# trigger_interface.net
KiCad netlist of a schematic drawn in Altium Designer
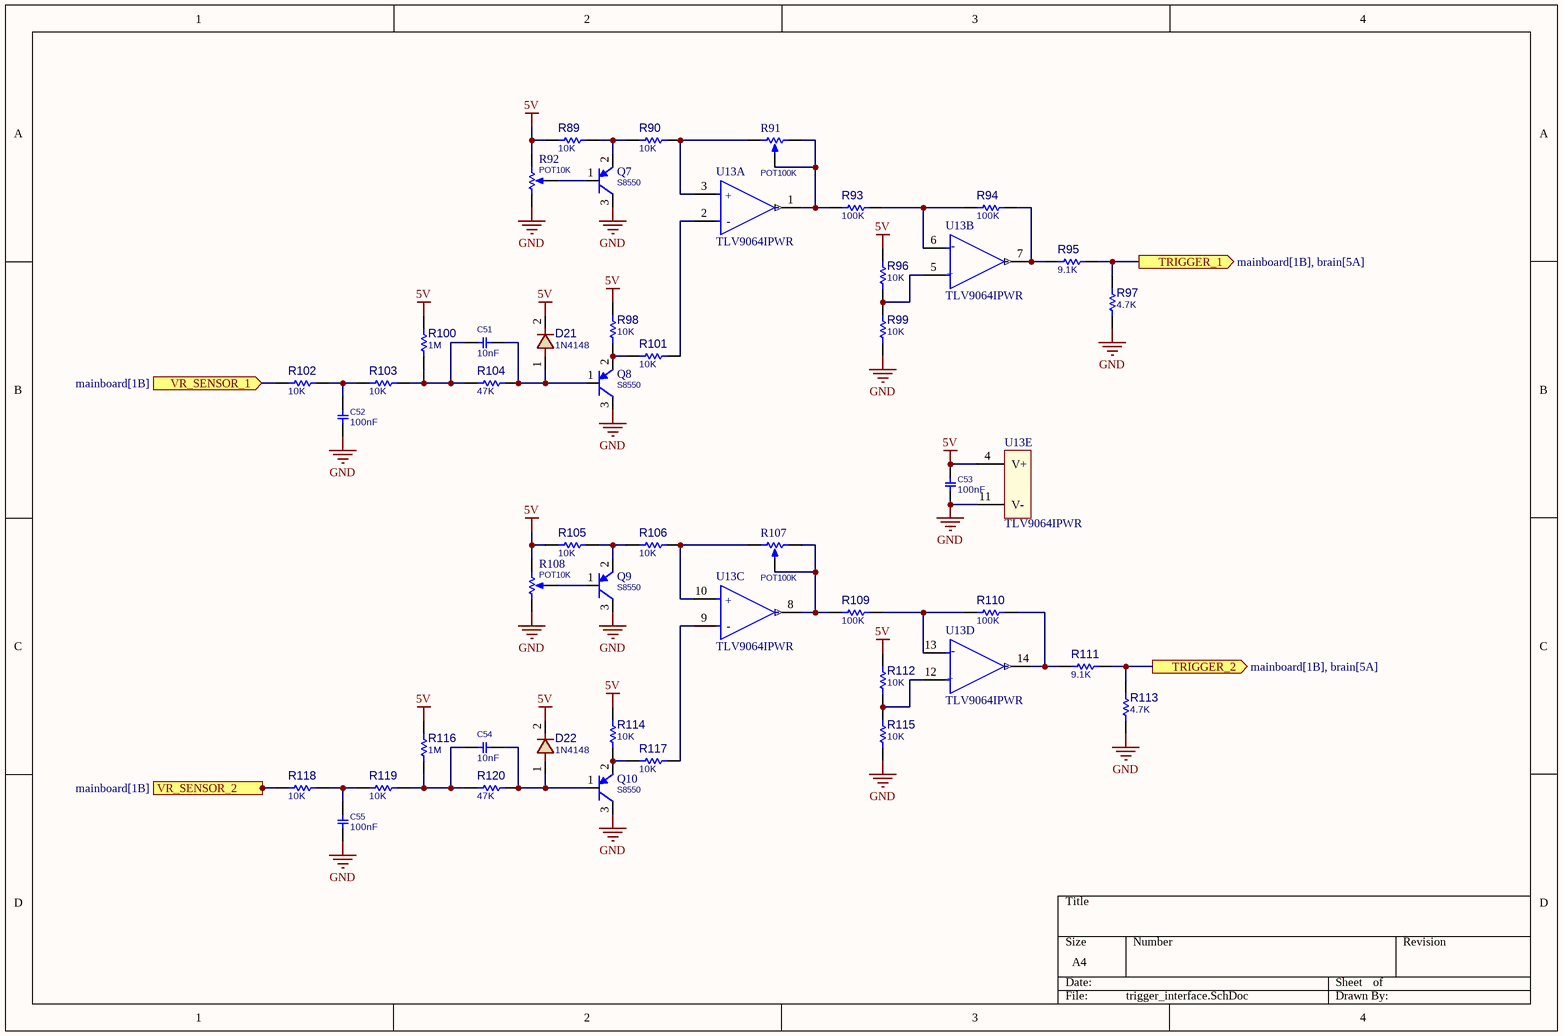
[diagram p0: trigger_interface.SchDoc]

(export (version "E")
  (design (tool "Eeschema 10.0.6"))
  (components
    (comp (ref "C51")
      (value "10nF")
      (footprint "C0805")
      (description "CAP, MLCC")
      (fields (field (name "MANF_P#") "MANF_PART#") (field (name "MANF") "Murata"))
      (libsource (lib "passive_smd") (part "CAP_SMD_MLCC"))
    )
    (comp (ref "C52")
      (value "100nF")
      (footprint "C0805")
      (description "CAP, MLCC")
      (fields (field (name "MANF_P#") "MANF_PART#") (field (name "MANF") "Murata"))
      (libsource (lib "passive_smd") (part "CAP_SMD_MLCC"))
    )
    (comp (ref "C53")
      (value "100nF")
      (footprint "C0805")
      (description "CAP, MLCC")
      (fields (field (name "MANF_P#") "MANF_PART#") (field (name "MANF") "Murata"))
      (libsource (lib "passive_smd") (part "CAP_SMD_MLCC"))
    )
    (comp (ref "C54")
      (value "10nF")
      (footprint "C0805")
      (description "CAP, MLCC")
      (fields (field (name "MANF_P#") "MANF_PART#") (field (name "MANF") "Murata"))
      (libsource (lib "passive_smd") (part "CAP_SMD_MLCC"))
    )
    (comp (ref "C55")
      (value "100nF")
      (footprint "C0805")
      (description "CAP, MLCC")
      (fields (field (name "MANF_P#") "MANF_PART#") (field (name "MANF") "Murata"))
      (libsource (lib "passive_smd") (part "CAP_SMD_MLCC"))
    )
    (comp (ref "D21")
      (value "1N4148")
      (footprint "D_SOD80")
      (description "DIODE, FAST SWTICHING, 0.3A, 0.5W")
      (fields (field (name "MANF") "MANF"))
      (libsource (lib "diode") (part "DIODE_SMD_1N4148_SOD80"))
    )
    (comp (ref "D22")
      (value "1N4148")
      (footprint "D_SOD80")
      (description "DIODE, FAST SWTICHING, 0.3A, 0.5W")
      (fields (field (name "MANF") "MANF"))
      (libsource (lib "diode") (part "DIODE_SMD_1N4148_SOD80"))
    )
    (comp (ref "Q7")
      (value "S8550")
      (footprint "SOT23_3")
      (description "BJT, PNP, 25v, 0.5A, SMD, SOT23")
      (libsource (lib "transistor_bjt") (part "PNP_S8550_SOT23"))
    )
    (comp (ref "Q8")
      (value "S8550")
      (footprint "SOT23_3")
      (description "BJT, PNP, 25v, 0.5A, SMD, SOT23")
      (libsource (lib "transistor_bjt") (part "PNP_S8550_SOT23"))
    )
    (comp (ref "Q9")
      (value "S8550")
      (footprint "SOT23_3")
      (description "BJT, PNP, 25v, 0.5A, SMD, SOT23")
      (libsource (lib "transistor_bjt") (part "PNP_S8550_SOT23"))
    )
    (comp (ref "Q10")
      (value "S8550")
      (footprint "SOT23_3")
      (description "BJT, PNP, 25v, 0.5A, SMD, SOT23")
      (libsource (lib "transistor_bjt") (part "PNP_S8550_SOT23"))
    )
    (comp (ref "R89")
      (value "10K")
      (footprint "R0805")
      (description "RESISTOR, SMD")
      (libsource (lib "passive_smd") (part "RES_SMD"))
    )
    (comp (ref "R90")
      (value "10K")
      (footprint "R0805")
      (description "RESISTOR, SMD")
      (libsource (lib "passive_smd") (part "RES_SMD"))
    )
    (comp (ref "R91")
      (value "POT100K")
      (footprint "POT_7X5")
      (description "RESISTOR, THD, Potentiometer")
      (libsource (lib "resistor_pot_trimmer") (part "RES_THD_POT_7X5"))
    )
    (comp (ref "R92")
      (value "POT10K")
      (footprint "POT_7X5")
      (description "RESISTOR, THD, Potentiometer")
      (libsource (lib "resistor_pot_trimmer") (part "RES_THD_POT_7X5"))
    )
    (comp (ref "R93")
      (value "100K")
      (footprint "R0805")
      (description "RESISTOR, SMD")
      (libsource (lib "passive_smd") (part "RES_SMD"))
    )
    (comp (ref "R94")
      (value "100K")
      (footprint "R0805")
      (description "RESISTOR, SMD")
      (libsource (lib "passive_smd") (part "RES_SMD"))
    )
    (comp (ref "R95")
      (value "9.1K")
      (footprint "R0805")
      (description "RESISTOR, SMD")
      (libsource (lib "passive_smd") (part "RES_SMD"))
    )
    (comp (ref "R96")
      (value "10K")
      (footprint "R0805")
      (description "RESISTOR, SMD")
      (libsource (lib "passive_smd") (part "RES_SMD"))
    )
    (comp (ref "R97")
      (value "4.7K")
      (footprint "R0805")
      (description "RESISTOR, SMD")
      (libsource (lib "passive_smd") (part "RES_SMD"))
    )
    (comp (ref "R98")
      (value "10K")
      (footprint "R0805")
      (description "RESISTOR, SMD")
      (libsource (lib "passive_smd") (part "RES_SMD"))
    )
    (comp (ref "R99")
      (value "10K")
      (footprint "R0805")
      (description "RESISTOR, SMD")
      (libsource (lib "passive_smd") (part "RES_SMD"))
    )
    (comp (ref "R100")
      (value "1M")
      (footprint "R0805")
      (description "RESISTOR, SMD")
      (libsource (lib "passive_smd") (part "RES_SMD"))
    )
    (comp (ref "R101")
      (value "10K")
      (footprint "R0805")
      (description "RESISTOR, SMD")
      (libsource (lib "passive_smd") (part "RES_SMD"))
    )
    (comp (ref "R102")
      (value "10K")
      (footprint "R0805")
      (description "RESISTOR, SMD")
      (libsource (lib "passive_smd") (part "RES_SMD"))
    )
    (comp (ref "R103")
      (value "10K")
      (footprint "R0805")
      (description "RESISTOR, SMD")
      (libsource (lib "passive_smd") (part "RES_SMD"))
    )
    (comp (ref "R104")
      (value "47K")
      (footprint "R0805")
      (description "RESISTOR, SMD")
      (libsource (lib "passive_smd") (part "RES_SMD"))
    )
    (comp (ref "R105")
      (value "10K")
      (footprint "R0805")
      (description "RESISTOR, SMD")
      (libsource (lib "passive_smd") (part "RES_SMD"))
    )
    (comp (ref "R106")
      (value "10K")
      (footprint "R0805")
      (description "RESISTOR, SMD")
      (libsource (lib "passive_smd") (part "RES_SMD"))
    )
    (comp (ref "R107")
      (value "POT100K")
      (footprint "POT_7X5")
      (description "RESISTOR, THD, Potentiometer")
      (libsource (lib "resistor_pot_trimmer") (part "RES_THD_POT_7X5"))
    )
    (comp (ref "R108")
      (value "POT10K")
      (footprint "POT_7X5")
      (description "RESISTOR, THD, Potentiometer")
      (libsource (lib "resistor_pot_trimmer") (part "RES_THD_POT_7X5"))
    )
    (comp (ref "R109")
      (value "100K")
      (footprint "R0805")
      (description "RESISTOR, SMD")
      (libsource (lib "passive_smd") (part "RES_SMD"))
    )
    (comp (ref "R110")
      (value "100K")
      (footprint "R0805")
      (description "RESISTOR, SMD")
      (libsource (lib "passive_smd") (part "RES_SMD"))
    )
    (comp (ref "R111")
      (value "9.1K")
      (footprint "R0805")
      (description "RESISTOR, SMD")
      (libsource (lib "passive_smd") (part "RES_SMD"))
    )
    (comp (ref "R112")
      (value "10K")
      (footprint "R0805")
      (description "RESISTOR, SMD")
      (libsource (lib "passive_smd") (part "RES_SMD"))
    )
    (comp (ref "R113")
      (value "4.7K")
      (footprint "R0805")
      (description "RESISTOR, SMD")
      (libsource (lib "passive_smd") (part "RES_SMD"))
    )
    (comp (ref "R114")
      (value "10K")
      (footprint "R0805")
      (description "RESISTOR, SMD")
      (libsource (lib "passive_smd") (part "RES_SMD"))
    )
    (comp (ref "R115")
      (value "10K")
      (footprint "R0805")
      (description "RESISTOR, SMD")
      (libsource (lib "passive_smd") (part "RES_SMD"))
    )
    (comp (ref "R116")
      (value "1M")
      (footprint "R0805")
      (description "RESISTOR, SMD")
      (libsource (lib "passive_smd") (part "RES_SMD"))
    )
    (comp (ref "R117")
      (value "10K")
      (footprint "R0805")
      (description "RESISTOR, SMD")
      (libsource (lib "passive_smd") (part "RES_SMD"))
    )
    (comp (ref "R118")
      (value "10K")
      (footprint "R0805")
      (description "RESISTOR, SMD")
      (libsource (lib "passive_smd") (part "RES_SMD"))
    )
    (comp (ref "R119")
      (value "10K")
      (footprint "R0805")
      (description "RESISTOR, SMD")
      (libsource (lib "passive_smd") (part "RES_SMD"))
    )
    (comp (ref "R120")
      (value "47K")
      (footprint "R0805")
      (description "RESISTOR, SMD")
      (libsource (lib "passive_smd") (part "RES_SMD"))
    )
    (comp (ref "U13")
      (value "TLV9064IPWR")
      (footprint "TTSOP-14")
      (description "IC CMOS 4 CIRCUIT 14TSSOP")
      (libsource (lib "Alib") (part "TLV9064"))
    )
  )
  (nets
    (net (code "1") (name "/TRIGGER_1") (class "Default")
      (node (ref "R95") (pin "2") (pinfunction "2_2") (pintype "passive"))
      (node (ref "R97") (pin "2") (pinfunction "2_2") (pintype "passive"))
    )
    (net (code "2") (name "/TRIGGER_2") (class "Default")
      (node (ref "R111") (pin "2") (pinfunction "2_2") (pintype "passive"))
      (node (ref "R113") (pin "2") (pinfunction "2_2") (pintype "passive"))
    )
    (net (code "3") (name "/VR_SENSOR_1") (class "Default")
      (node (ref "R102") (pin "2") (pinfunction "2_2") (pintype "passive"))
    )
    (net (code "4") (name "/VR_SENSOR_2") (class "Default")
      (node (ref "R118") (pin "2") (pinfunction "2_2") (pintype "passive"))
    )
    (net (code "5") (name "5V") (class "Default")
      (node (ref "C53") (pin "2") (pinfunction "2_2") (pintype "passive"))
      (node (ref "D21") (pin "2") (pinfunction "2_2") (pintype "passive"))
      (node (ref "D22") (pin "2") (pinfunction "2_2") (pintype "passive"))
      (node (ref "R100") (pin "1") (pinfunction "1_1") (pintype "passive"))
      (node (ref "R105") (pin "1") (pinfunction "1_1") (pintype "passive"))
      (node (ref "R108") (pin "3") (pinfunction "BOT_3") (pintype "passive"))
      (node (ref "R112") (pin "2") (pinfunction "2_2") (pintype "passive"))
      (node (ref "R114") (pin "1") (pinfunction "1_1") (pintype "passive"))
      (node (ref "R116") (pin "1") (pinfunction "1_1") (pintype "passive"))
      (node (ref "R89") (pin "1") (pinfunction "1_1") (pintype "passive"))
      (node (ref "R92") (pin "3") (pinfunction "BOT_3") (pintype "passive"))
      (node (ref "R96") (pin "2") (pinfunction "2_2") (pintype "passive"))
      (node (ref "R98") (pin "1") (pinfunction "1_1") (pintype "passive"))
      (node (ref "U13") (pin "4") (pinfunction "V+_4") (pintype "power_in"))
    )
    (net (code "6") (name "GND") (class "Default")
      (node (ref "C52") (pin "1") (pinfunction "1_1") (pintype "passive"))
      (node (ref "C53") (pin "1") (pinfunction "1_1") (pintype "passive"))
      (node (ref "C55") (pin "1") (pinfunction "1_1") (pintype "passive"))
      (node (ref "Q10") (pin "3") (pinfunction "C_3") (pintype "passive"))
      (node (ref "Q7") (pin "3") (pinfunction "C_3") (pintype "passive"))
      (node (ref "Q8") (pin "3") (pinfunction "C_3") (pintype "passive"))
      (node (ref "Q9") (pin "3") (pinfunction "C_3") (pintype "passive"))
      (node (ref "R108") (pin "1") (pinfunction "TOP_1") (pintype "passive"))
      (node (ref "R113") (pin "1") (pinfunction "1_1") (pintype "passive"))
      (node (ref "R115") (pin "2") (pinfunction "2_2") (pintype "passive"))
      (node (ref "R92") (pin "1") (pinfunction "TOP_1") (pintype "passive"))
      (node (ref "R97") (pin "1") (pinfunction "1_1") (pintype "passive"))
      (node (ref "R99") (pin "2") (pinfunction "2_2") (pintype "passive"))
      (node (ref "U13") (pin "11") (pinfunction "V-_11") (pintype "power_in"))
    )
    (net (code "7") (name "Net-(C51-Pad2)") (class "Default")
      (node (ref "C51") (pin "2") (pinfunction "2_2") (pintype "passive"))
      (node (ref "R100") (pin "2") (pinfunction "2_2") (pintype "passive"))
      (node (ref "R103") (pin "1") (pinfunction "1_1") (pintype "passive"))
      (node (ref "R104") (pin "2") (pinfunction "2_2") (pintype "passive"))
    )
    (net (code "8") (name "Net-(C52-Pad2)") (class "Default")
      (node (ref "C52") (pin "2") (pinfunction "2_2") (pintype "passive"))
      (node (ref "R102") (pin "1") (pinfunction "1_1") (pintype "passive"))
      (node (ref "R103") (pin "2") (pinfunction "2_2") (pintype "passive"))
    )
    (net (code "9") (name "Net-(C54-Pad2)") (class "Default")
      (node (ref "C54") (pin "2") (pinfunction "2_2") (pintype "passive"))
      (node (ref "R116") (pin "2") (pinfunction "2_2") (pintype "passive"))
      (node (ref "R119") (pin "1") (pinfunction "1_1") (pintype "passive"))
      (node (ref "R120") (pin "2") (pinfunction "2_2") (pintype "passive"))
    )
    (net (code "10") (name "Net-(C55-Pad2)") (class "Default")
      (node (ref "C55") (pin "2") (pinfunction "2_2") (pintype "passive"))
      (node (ref "R118") (pin "1") (pinfunction "1_1") (pintype "passive"))
      (node (ref "R119") (pin "2") (pinfunction "2_2") (pintype "passive"))
    )
    (net (code "11") (name "Net-(Q7-B)") (class "Default")
      (node (ref "Q7") (pin "1") (pinfunction "B_1") (pintype "passive"))
      (node (ref "R92") (pin "2") (pinfunction "TAP_2") (pintype "passive"))
    )
    (net (code "12") (name "Net-(Q7-E)") (class "Default")
      (node (ref "Q7") (pin "2") (pinfunction "E_2") (pintype "passive"))
      (node (ref "R89") (pin "2") (pinfunction "2_2") (pintype "passive"))
      (node (ref "R90") (pin "1") (pinfunction "1_1") (pintype "passive"))
    )
    (net (code "13") (name "Net-(Q8-B)") (class "Default")
      (node (ref "C51") (pin "1") (pinfunction "1_1") (pintype "passive"))
      (node (ref "D21") (pin "1") (pinfunction "1_1") (pintype "passive"))
      (node (ref "Q8") (pin "1") (pinfunction "B_1") (pintype "passive"))
      (node (ref "R104") (pin "1") (pinfunction "1_1") (pintype "passive"))
    )
    (net (code "14") (name "Net-(Q8-E)") (class "Default")
      (node (ref "Q8") (pin "2") (pinfunction "E_2") (pintype "passive"))
      (node (ref "R101") (pin "1") (pinfunction "1_1") (pintype "passive"))
      (node (ref "R98") (pin "2") (pinfunction "2_2") (pintype "passive"))
    )
    (net (code "15") (name "Net-(Q9-B)") (class "Default")
      (node (ref "Q9") (pin "1") (pinfunction "B_1") (pintype "passive"))
      (node (ref "R108") (pin "2") (pinfunction "TAP_2") (pintype "passive"))
    )
    (net (code "16") (name "Net-(Q9-E)") (class "Default")
      (node (ref "Q9") (pin "2") (pinfunction "E_2") (pintype "passive"))
      (node (ref "R105") (pin "2") (pinfunction "2_2") (pintype "passive"))
      (node (ref "R106") (pin "1") (pinfunction "1_1") (pintype "passive"))
    )
    (net (code "17") (name "Net-(Q10-B)") (class "Default")
      (node (ref "C54") (pin "1") (pinfunction "1_1") (pintype "passive"))
      (node (ref "D22") (pin "1") (pinfunction "1_1") (pintype "passive"))
      (node (ref "Q10") (pin "1") (pinfunction "B_1") (pintype "passive"))
      (node (ref "R120") (pin "1") (pinfunction "1_1") (pintype "passive"))
    )
    (net (code "18") (name "Net-(Q10-E)") (class "Default")
      (node (ref "Q10") (pin "2") (pinfunction "E_2") (pintype "passive"))
      (node (ref "R114") (pin "2") (pinfunction "2_2") (pintype "passive"))
      (node (ref "R117") (pin "1") (pinfunction "1_1") (pintype "passive"))
    )
    (net (code "19") (name "Net-(R91-BOT)") (class "Default")
      (node (ref "R91") (pin "2") (pinfunction "TAP_2") (pintype "passive"))
      (node (ref "R91") (pin "3") (pinfunction "BOT_3") (pintype "passive"))
      (node (ref "R93") (pin "1") (pinfunction "1_1") (pintype "passive"))
      (node (ref "U13") (pin "1") (pinfunction "OUT1_1") (pintype "output"))
    )
    (net (code "20") (name "Net-(R91-TOP)") (class "Default")
      (node (ref "R90") (pin "2") (pinfunction "2_2") (pintype "passive"))
      (node (ref "R91") (pin "1") (pinfunction "TOP_1") (pintype "passive"))
      (node (ref "U13") (pin "3") (pinfunction "IN1+_3") (pintype "tri_state"))
    )
    (net (code "21") (name "Net-(R107-BOT)") (class "Default")
      (node (ref "R107") (pin "2") (pinfunction "TAP_2") (pintype "passive"))
      (node (ref "R107") (pin "3") (pinfunction "BOT_3") (pintype "passive"))
      (node (ref "R109") (pin "1") (pinfunction "1_1") (pintype "passive"))
      (node (ref "U13") (pin "8") (pinfunction "OUT3_8") (pintype "output"))
    )
    (net (code "22") (name "Net-(R107-TOP)") (class "Default")
      (node (ref "R106") (pin "2") (pinfunction "2_2") (pintype "passive"))
      (node (ref "R107") (pin "1") (pinfunction "TOP_1") (pintype "passive"))
      (node (ref "U13") (pin "10") (pinfunction "IN3+_10") (pintype "tri_state"))
    )
    (net (code "23") (name "Net-(U13A-IN1-)") (class "Default")
      (node (ref "R101") (pin "2") (pinfunction "2_2") (pintype "passive"))
      (node (ref "U13") (pin "2") (pinfunction "IN1-_2") (pintype "tri_state"))
    )
    (net (code "24") (name "Net-(U13B-IN2+)") (class "Default")
      (node (ref "R96") (pin "1") (pinfunction "1_1") (pintype "passive"))
      (node (ref "R99") (pin "1") (pinfunction "1_1") (pintype "passive"))
      (node (ref "U13") (pin "5") (pinfunction "IN2+_5") (pintype "tri_state"))
    )
    (net (code "25") (name "Net-(U13B-IN2-)") (class "Default")
      (node (ref "R93") (pin "2") (pinfunction "2_2") (pintype "passive"))
      (node (ref "R94") (pin "1") (pinfunction "1_1") (pintype "passive"))
      (node (ref "U13") (pin "6") (pinfunction "IN2-_6") (pintype "tri_state"))
    )
    (net (code "26") (name "Net-(U13B-OUT2)") (class "Default")
      (node (ref "R94") (pin "2") (pinfunction "2_2") (pintype "passive"))
      (node (ref "R95") (pin "1") (pinfunction "1_1") (pintype "passive"))
      (node (ref "U13") (pin "7") (pinfunction "OUT2_7") (pintype "output"))
    )
    (net (code "27") (name "Net-(U13C-IN3-)") (class "Default")
      (node (ref "R117") (pin "2") (pinfunction "2_2") (pintype "passive"))
      (node (ref "U13") (pin "9") (pinfunction "IN3-_9") (pintype "tri_state"))
    )
    (net (code "28") (name "Net-(U13D-IN4+)") (class "Default")
      (node (ref "R112") (pin "1") (pinfunction "1_1") (pintype "passive"))
      (node (ref "R115") (pin "1") (pinfunction "1_1") (pintype "passive"))
      (node (ref "U13") (pin "12") (pinfunction "IN4+_12") (pintype "tri_state"))
    )
    (net (code "29") (name "Net-(U13D-IN4-)") (class "Default")
      (node (ref "R109") (pin "2") (pinfunction "2_2") (pintype "passive"))
      (node (ref "R110") (pin "1") (pinfunction "1_1") (pintype "passive"))
      (node (ref "U13") (pin "13") (pinfunction "IN4-_13") (pintype "tri_state"))
    )
    (net (code "30") (name "Net-(U13D-OUT4)") (class "Default")
      (node (ref "R110") (pin "2") (pinfunction "2_2") (pintype "passive"))
      (node (ref "R111") (pin "1") (pinfunction "1_1") (pintype "passive"))
      (node (ref "U13") (pin "14") (pinfunction "OUT4_14") (pintype "output"))
    )
  )
)
